# riser-1u-ethernet.net
KiCad netlist of a schematic drawn in EAGLE
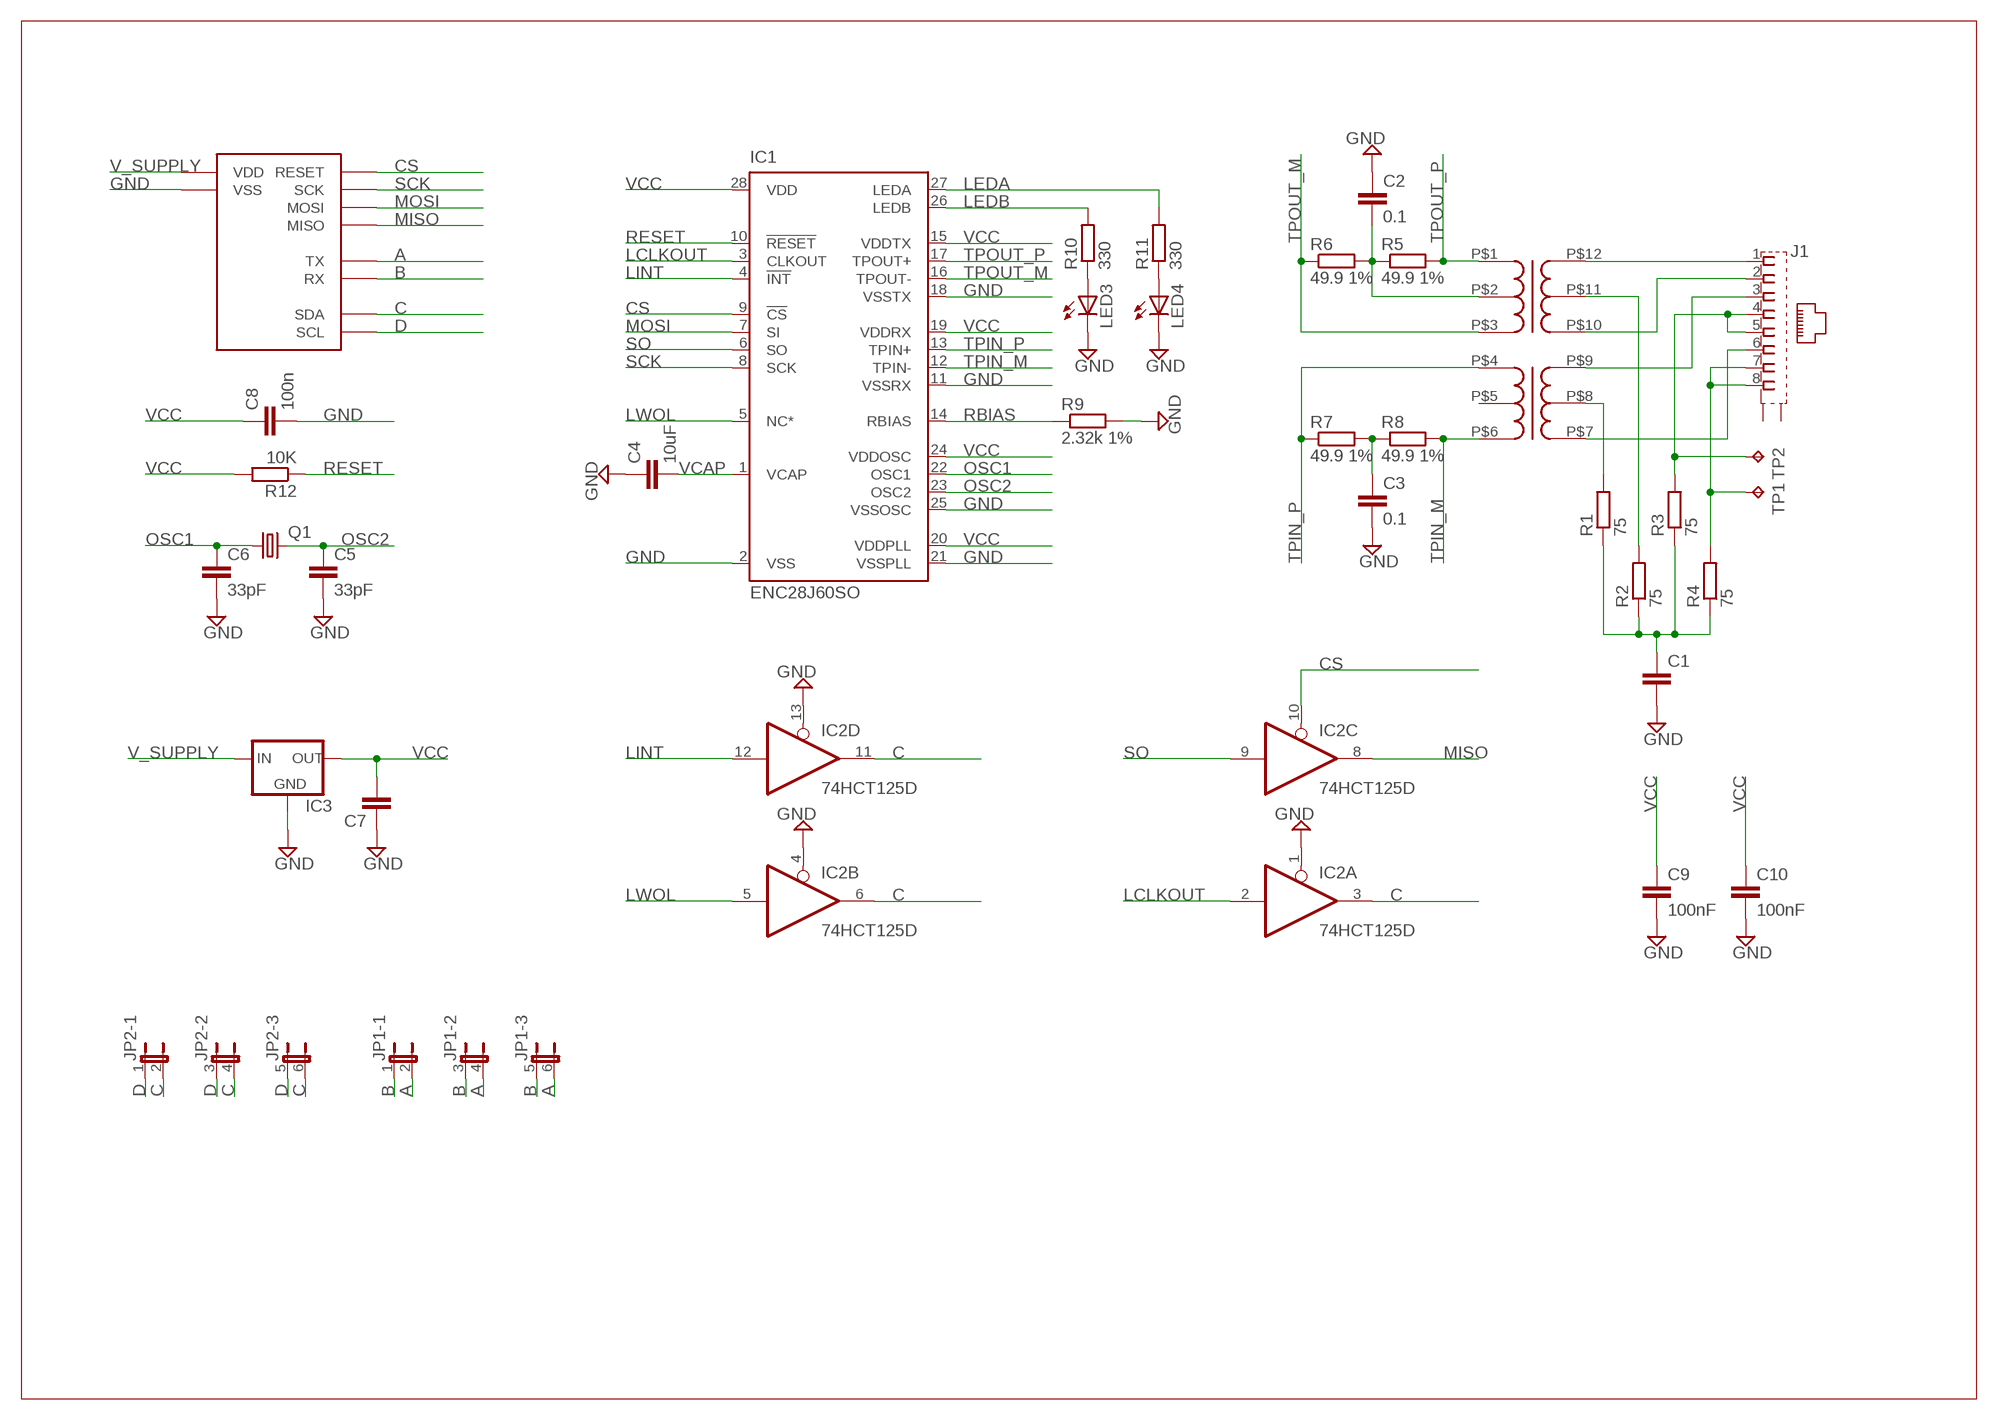
[diagram p0: schematic, sheet 1]

(export (version "E")
  (design (tool "Eeschema 10.0.6"))
  (components
    (comp (ref "C1")
      (value "C-EU075-032X103")
      (footprint "eagle-import:C075-032X103")
      (libsource (lib "eagle-import") (part "C-EU075-032X103"))
    )
    (comp (ref "C2")
      (value "0.1")
      (footprint "eagle-import:C0805")
      (libsource (lib "eagle-import") (part "C-EUC0805"))
    )
    (comp (ref "C3")
      (value "0.1")
      (footprint "eagle-import:C0805")
      (libsource (lib "eagle-import") (part "C-EUC0805"))
    )
    (comp (ref "C4")
      (value "10uF")
      (footprint "eagle-import:C1206")
      (libsource (lib "eagle-import") (part "C-EUC1206"))
    )
    (comp (ref "C5")
      (value "33pF")
      (footprint "eagle-import:C0805")
      (libsource (lib "eagle-import") (part "C-EUC0805"))
    )
    (comp (ref "C6")
      (value "33pF")
      (footprint "eagle-import:C0805")
      (libsource (lib "eagle-import") (part "C-EUC0805"))
    )
    (comp (ref "C7")
      (value "C-EUC1206")
      (footprint "eagle-import:C1206")
      (libsource (lib "eagle-import") (part "C-EUC1206"))
    )
    (comp (ref "C8")
      (value "100n")
      (footprint "eagle-import:C0805")
      (libsource (lib "eagle-import") (part "C-EUC0805"))
    )
    (comp (ref "C9")
      (value "100nF")
      (footprint "eagle-import:C0805")
      (libsource (lib "eagle-import") (part "C-EUC0805"))
    )
    (comp (ref "C10")
      (value "100nF")
      (footprint "eagle-import:C0805")
      (libsource (lib "eagle-import") (part "C-EUC0805"))
    )
    (comp (ref "IC1")
      (value "ENC28J60SO")
      (footprint "eagle-import:SO28W")
      (libsource (lib "eagle-import") (part "ENC28J60SO"))
    )
    (comp (ref "IC2")
      (value "74HCT125D")
      (footprint "eagle-import:SO14")
      (libsource (lib "eagle-import") (part "74125DHCT"))
    )
    (comp (ref "IC3")
      (value "LM1117TO252")
      (footprint "eagle-import:TO252")
      (libsource (lib "eagle-import") (part "LM1117TO252"))
    )
    (comp (ref "J1")
      (value "555153-1")
      (footprint "eagle-import:555153-1")
      (libsource (lib "eagle-import") (part "555153-1"))
    )
    (comp (ref "JP1")
      (value "JP3QE")
      (footprint "eagle-import:JP3Q")
      (libsource (lib "eagle-import") (part "JP3QE"))
    )
    (comp (ref "JP2")
      (value "JP3QE")
      (footprint "eagle-import:JP3Q")
      (libsource (lib "eagle-import") (part "JP3QE"))
    )
    (comp (ref "LED3")
      (value "LED3MM")
      (footprint "eagle-import:LED3MM")
      (libsource (lib "eagle-import") (part "LED3MM"))
    )
    (comp (ref "LED4")
      (value "LED3MM")
      (footprint "eagle-import:LED3MM")
      (libsource (lib "eagle-import") (part "LED3MM"))
    )
    (comp (ref "Q1")
      (value "CRYSTALHC49S")
      (footprint "eagle-import:HC49_S")
      (libsource (lib "eagle-import") (part "CRYSTALHC49S"))
    )
    (comp (ref "R1")
      (value "75")
      (footprint "eagle-import:R0805")
      (libsource (lib "eagle-import") (part "R-EU_R0805"))
    )
    (comp (ref "R2")
      (value "75")
      (footprint "eagle-import:R0805")
      (libsource (lib "eagle-import") (part "R-EU_R0805"))
    )
    (comp (ref "R3")
      (value "75")
      (footprint "eagle-import:R0805")
      (libsource (lib "eagle-import") (part "R-EU_R0805"))
    )
    (comp (ref "R4")
      (value "75")
      (footprint "eagle-import:R0805")
      (libsource (lib "eagle-import") (part "R-EU_R0805"))
    )
    (comp (ref "R5")
      (value "49.9 1%")
      (footprint "eagle-import:R0805")
      (libsource (lib "eagle-import") (part "R-EU_R0805"))
    )
    (comp (ref "R6")
      (value "49.9 1%")
      (footprint "eagle-import:R0805")
      (libsource (lib "eagle-import") (part "R-EU_R0805"))
    )
    (comp (ref "R7")
      (value "49.9 1%")
      (footprint "eagle-import:R0805")
      (libsource (lib "eagle-import") (part "R-EU_R0805"))
    )
    (comp (ref "R8")
      (value "49.9 1%")
      (footprint "eagle-import:R0805")
      (libsource (lib "eagle-import") (part "R-EU_R0805"))
    )
    (comp (ref "R9")
      (value "2.32k 1%")
      (footprint "eagle-import:R0805")
      (libsource (lib "eagle-import") (part "R-EU_R0805"))
    )
    (comp (ref "R10")
      (value "330")
      (footprint "eagle-import:R0805")
      (libsource (lib "eagle-import") (part "R-EU_R0805"))
    )
    (comp (ref "R11")
      (value "330")
      (footprint "eagle-import:R0805")
      (libsource (lib "eagle-import") (part "R-EU_R0805"))
    )
    (comp (ref "R12")
      (value "10K")
      (footprint "eagle-import:R0805")
      (libsource (lib "eagle-import") (part "R-EU_R0805"))
    )
    (comp (ref "TP1")
      (value "TPPAD1-13")
      (footprint "eagle-import:P1-13")
      (libsource (lib "eagle-import") (part "TPPAD1-13"))
    )
    (comp (ref "TP2")
      (value "TPPAD1-13")
      (footprint "eagle-import:P1-13")
      (libsource (lib "eagle-import") (part "TPPAD1-13"))
    )
    (comp (ref "U$1")
      (value "UNI_BOARD_CONNECTOR_10")
      (footprint "eagle-import:UNI_BOARD_CONN_10")
      (libsource (lib "eagle-import") (part "UNI_BOARD_CONNECTOR_10"))
    )
    (comp (ref "U$2")
      (value "ETHERNET_TRANSFORMER")
      (footprint "eagle-import:DIL-16-TRANSFORMER")
      (libsource (lib "eagle-import") (part "ETHERNET_TRANSFORMER"))
    )
  )
  (nets
    (net (code "1") (name "/A") (class "Default")
      (node (ref "JP1") (pin "2") (pinfunction "2_2") (pintype "passive"))
      (node (ref "JP1") (pin "4") (pinfunction "2_4") (pintype "passive"))
      (node (ref "JP1") (pin "6") (pinfunction "2_6") (pintype "passive"))
      (node (ref "U$1") (pin "C$7") (pinfunction "TX_C$7") (pintype "bidirectional"))
    )
    (net (code "2") (name "/B") (class "Default")
      (node (ref "JP1") (pin "1") (pinfunction "1_1") (pintype "passive"))
      (node (ref "JP1") (pin "3") (pinfunction "1_3") (pintype "passive"))
      (node (ref "JP1") (pin "5") (pinfunction "1_5") (pintype "passive"))
      (node (ref "U$1") (pin "C$9") (pinfunction "RX_C$9") (pintype "bidirectional"))
    )
    (net (code "3") (name "/C") (class "Default")
      (node (ref "IC2") (pin "11") (pinfunction "O_11") (pintype "tri_state"))
      (node (ref "IC2") (pin "3") (pinfunction "O_3") (pintype "tri_state"))
      (node (ref "IC2") (pin "6") (pinfunction "O_6") (pintype "tri_state"))
      (node (ref "JP2") (pin "2") (pinfunction "2_2") (pintype "passive"))
      (node (ref "JP2") (pin "4") (pinfunction "2_4") (pintype "passive"))
      (node (ref "JP2") (pin "6") (pinfunction "2_6") (pintype "passive"))
      (node (ref "U$1") (pin "C$8") (pinfunction "SDA_C$8") (pintype "bidirectional"))
    )
    (net (code "4") (name "/CS") (class "Default")
      (node (ref "IC1") (pin "9") (pinfunction "~{CS}_9") (pintype "input"))
      (node (ref "IC2") (pin "10") (pinfunction "OE_10") (pintype "input"))
      (node (ref "U$1") (pin "C$5") (pinfunction "RESET_C$5") (pintype "bidirectional"))
    )
    (net (code "5") (name "/D") (class "Default")
      (node (ref "JP2") (pin "1") (pinfunction "1_1") (pintype "passive"))
      (node (ref "JP2") (pin "3") (pinfunction "1_3") (pintype "passive"))
      (node (ref "JP2") (pin "5") (pinfunction "1_5") (pintype "passive"))
      (node (ref "U$1") (pin "C$10") (pinfunction "SCL_C$10") (pintype "bidirectional"))
    )
    (net (code "6") (name "/LCLKOUT") (class "Default")
      (node (ref "IC1") (pin "3") (pinfunction "CLKOUT_3") (pintype "output"))
      (node (ref "IC2") (pin "2") (pinfunction "I_2") (pintype "input"))
    )
    (net (code "7") (name "/LEDA") (class "Default")
      (node (ref "IC1") (pin "27") (pinfunction "LEDA_27") (pintype "output"))
      (node (ref "R11") (pin "2") (pinfunction "2_2") (pintype "passive"))
    )
    (net (code "8") (name "/LEDB") (class "Default")
      (node (ref "IC1") (pin "26") (pinfunction "LEDB_26") (pintype "output"))
      (node (ref "R10") (pin "2") (pinfunction "2_2") (pintype "passive"))
    )
    (net (code "9") (name "/LINT") (class "Default")
      (node (ref "IC1") (pin "4") (pinfunction "~{INT}_4") (pintype "output"))
      (node (ref "IC2") (pin "12") (pinfunction "I_12") (pintype "input"))
    )
    (net (code "10") (name "/LWOL") (class "Default")
      (node (ref "IC1") (pin "5") (pinfunction "NC*_5") (pintype "output"))
      (node (ref "IC2") (pin "5") (pinfunction "I_5") (pintype "input"))
    )
    (net (code "11") (name "/MISO") (class "Default")
      (node (ref "IC2") (pin "8") (pinfunction "O_8") (pintype "tri_state"))
      (node (ref "U$1") (pin "C$1") (pinfunction "MISO_C$1") (pintype "bidirectional"))
    )
    (net (code "12") (name "/MOSI") (class "Default")
      (node (ref "IC1") (pin "7") (pinfunction "SI_7") (pintype "input"))
      (node (ref "U$1") (pin "C$4") (pinfunction "MOSI_C$4") (pintype "bidirectional"))
    )
    (net (code "13") (name "/OSC1") (class "Default")
      (node (ref "C6") (pin "1") (pinfunction "1_1") (pintype "passive"))
      (node (ref "IC1") (pin "22") (pinfunction "OSC1_22") (pintype "input"))
      (node (ref "Q1") (pin "1") (pinfunction "1_1") (pintype "passive"))
    )
    (net (code "14") (name "/OSC2") (class "Default")
      (node (ref "C5") (pin "1") (pinfunction "1_1") (pintype "passive"))
      (node (ref "IC1") (pin "23") (pinfunction "OSC2_23") (pintype "output"))
      (node (ref "Q1") (pin "2") (pinfunction "2_2") (pintype "passive"))
    )
    (net (code "15") (name "/RBIAS") (class "Default")
      (node (ref "IC1") (pin "14") (pinfunction "RBIAS_14") (pintype "input"))
      (node (ref "R9") (pin "1") (pinfunction "1_1") (pintype "passive"))
    )
    (net (code "16") (name "/RESET") (class "Default")
      (node (ref "IC1") (pin "10") (pinfunction "~{RESET}_10") (pintype "input"))
      (node (ref "R12") (pin "1") (pinfunction "1_1") (pintype "passive"))
    )
    (net (code "17") (name "/SCK") (class "Default")
      (node (ref "IC1") (pin "8") (pinfunction "SCK_8") (pintype "input"))
      (node (ref "U$1") (pin "C$3") (pinfunction "SCK_C$3") (pintype "bidirectional"))
    )
    (net (code "18") (name "/SO") (class "Default")
      (node (ref "IC1") (pin "6") (pinfunction "SO_6") (pintype "output"))
      (node (ref "IC2") (pin "9") (pinfunction "I_9") (pintype "input"))
    )
    (net (code "19") (name "/TPIN_M") (class "Default")
      (node (ref "IC1") (pin "12") (pinfunction "TPIN-_12") (pintype "input"))
      (node (ref "R8") (pin "2") (pinfunction "2_2") (pintype "passive"))
      (node (ref "U$2") (pin "P$6") (pinfunction "P8_P$6") (pintype "bidirectional"))
    )
    (net (code "20") (name "/TPIN_P") (class "Default")
      (node (ref "IC1") (pin "13") (pinfunction "TPIN+_13") (pintype "input"))
      (node (ref "R7") (pin "1") (pinfunction "1_1") (pintype "passive"))
      (node (ref "U$2") (pin "P$4") (pinfunction "P6_P$4") (pintype "bidirectional"))
    )
    (net (code "21") (name "/TPOUT_M") (class "Default")
      (node (ref "IC1") (pin "16") (pinfunction "TPOUT-_16") (pintype "output"))
      (node (ref "R6") (pin "1") (pinfunction "1_1") (pintype "passive"))
      (node (ref "U$2") (pin "P$3") (pinfunction "P3_P$3") (pintype "bidirectional"))
    )
    (net (code "22") (name "/TPOUT_P") (class "Default")
      (node (ref "IC1") (pin "17") (pinfunction "TPOUT+_17") (pintype "output"))
      (node (ref "R5") (pin "2") (pinfunction "2_2") (pintype "passive"))
      (node (ref "U$2") (pin "P$1") (pinfunction "P1_P$1") (pintype "bidirectional"))
    )
    (net (code "23") (name "/VCAP") (class "Default")
      (node (ref "C4") (pin "2") (pinfunction "2_2") (pintype "passive"))
      (node (ref "IC1") (pin "1") (pinfunction "VCAP_1") (pintype "input"))
    )
    (net (code "24") (name "/VCC") (class "Default")
      (node (ref "C10") (pin "1") (pinfunction "1_1") (pintype "passive"))
      (node (ref "C7") (pin "2") (pinfunction "2_2") (pintype "passive"))
      (node (ref "C8") (pin "1") (pinfunction "1_1") (pintype "passive"))
      (node (ref "C9") (pin "1") (pinfunction "1_1") (pintype "passive"))
      (node (ref "IC1") (pin "15") (pinfunction "VDDTX_15") (pintype "input"))
      (node (ref "IC1") (pin "19") (pinfunction "VDDRX_19") (pintype "input"))
      (node (ref "IC1") (pin "20") (pinfunction "VDDPLL_20") (pintype "input"))
      (node (ref "IC1") (pin "24") (pinfunction "VDDOSC_24") (pintype "input"))
      (node (ref "IC1") (pin "28") (pinfunction "VDD_28") (pintype "input"))
      (node (ref "IC3") (pin "3") (pinfunction "OUT_3") (pintype "passive"))
      (node (ref "R12") (pin "2") (pinfunction "2_2") (pintype "passive"))
    )
    (net (code "25") (name "/V_SUPPLY") (class "Default")
      (node (ref "IC3") (pin "2") (pinfunction "IN_2") (pintype "input"))
      (node (ref "U$1") (pin "C$2") (pinfunction "VDD_C$2") (pintype "power_in"))
    )
    (net (code "26") (name "GND") (class "Default")
      (node (ref "C1") (pin "2") (pinfunction "2_2") (pintype "passive"))
      (node (ref "C10") (pin "2") (pinfunction "2_2") (pintype "passive"))
      (node (ref "C2") (pin "1") (pinfunction "1_1") (pintype "passive"))
      (node (ref "C3") (pin "2") (pinfunction "2_2") (pintype "passive"))
      (node (ref "C4") (pin "1") (pinfunction "1_1") (pintype "passive"))
      (node (ref "C5") (pin "2") (pinfunction "2_2") (pintype "passive"))
      (node (ref "C6") (pin "2") (pinfunction "2_2") (pintype "passive"))
      (node (ref "C7") (pin "1") (pinfunction "1_1") (pintype "passive"))
      (node (ref "C8") (pin "2") (pinfunction "2_2") (pintype "passive"))
      (node (ref "C9") (pin "2") (pinfunction "2_2") (pintype "passive"))
      (node (ref "IC1") (pin "11") (pinfunction "VSSRX_11") (pintype "input"))
      (node (ref "IC1") (pin "18") (pinfunction "VSSTX_18") (pintype "input"))
      (node (ref "IC1") (pin "2") (pinfunction "VSS_2") (pintype "input"))
      (node (ref "IC1") (pin "21") (pinfunction "VSSPLL_21") (pintype "input"))
      (node (ref "IC1") (pin "25") (pinfunction "VSSOSC_25") (pintype "input"))
      (node (ref "IC2") (pin "1") (pinfunction "OE_1") (pintype "input"))
      (node (ref "IC2") (pin "13") (pinfunction "OE_13") (pintype "input"))
      (node (ref "IC2") (pin "4") (pinfunction "OE_4") (pintype "input"))
      (node (ref "IC3") (pin "1") (pinfunction "GND_1") (pintype "input"))
      (node (ref "LED3") (pin "K") (pinfunction "C_K") (pintype "passive"))
      (node (ref "LED4") (pin "K") (pinfunction "C_K") (pintype "passive"))
      (node (ref "R9") (pin "2") (pinfunction "2_2") (pintype "passive"))
      (node (ref "U$1") (pin "C$6") (pinfunction "VSS_C$6") (pintype "power_in"))
    )
    (net (code "27") (name "Net-(C1-Pad1)") (class "Default")
      (node (ref "C1") (pin "1") (pinfunction "1_1") (pintype "passive"))
      (node (ref "R1") (pin "1") (pinfunction "1_1") (pintype "passive"))
      (node (ref "R2") (pin "1") (pinfunction "1_1") (pintype "passive"))
      (node (ref "R3") (pin "1") (pinfunction "1_1") (pintype "passive"))
      (node (ref "R4") (pin "1") (pinfunction "1_1") (pintype "passive"))
    )
    (net (code "28") (name "Net-(C3-Pad1)") (class "Default")
      (node (ref "C3") (pin "1") (pinfunction "1_1") (pintype "passive"))
      (node (ref "R7") (pin "2") (pinfunction "2_2") (pintype "passive"))
      (node (ref "R8") (pin "1") (pinfunction "1_1") (pintype "passive"))
    )
    (net (code "29") (name "Net-(J1-Pad4)") (class "Default")
      (node (ref "J1") (pin "4") (pinfunction "4_4") (pintype "passive"))
      (node (ref "J1") (pin "5") (pinfunction "5_5") (pintype "passive"))
      (node (ref "R3") (pin "2") (pinfunction "2_2") (pintype "passive"))
      (node (ref "TP2") (pin "TP") (pinfunction "TP_TP") (pintype "input"))
    )
    (net (code "30") (name "Net-(J1-Pad7)") (class "Default")
      (node (ref "J1") (pin "7") (pinfunction "7_7") (pintype "passive"))
      (node (ref "J1") (pin "8") (pinfunction "8_8") (pintype "passive"))
      (node (ref "R4") (pin "2") (pinfunction "2_2") (pintype "passive"))
      (node (ref "TP1") (pin "TP") (pinfunction "TP_TP") (pintype "input"))
    )
    (net (code "31") (name "Net-(LED3-PadA)") (class "Default")
      (node (ref "LED3") (pin "A") (pinfunction "A_A") (pintype "passive"))
      (node (ref "R10") (pin "1") (pinfunction "1_1") (pintype "passive"))
    )
    (net (code "32") (name "Net-(LED4-PadA)") (class "Default")
      (node (ref "LED4") (pin "A") (pinfunction "A_A") (pintype "passive"))
      (node (ref "R11") (pin "1") (pinfunction "1_1") (pintype "passive"))
    )
    (net (code "33") (name "Net-(U$2-P2)") (class "Default")
      (node (ref "C2") (pin "2") (pinfunction "2_2") (pintype "passive"))
      (node (ref "R5") (pin "1") (pinfunction "1_1") (pintype "passive"))
      (node (ref "R6") (pin "2") (pinfunction "2_2") (pintype "passive"))
      (node (ref "U$2") (pin "P$2") (pinfunction "P2_P$2") (pintype "bidirectional"))
    )
    (net (code "34") (name "Net-(U$2-P9)") (class "Default")
      (node (ref "J1") (pin "6") (pinfunction "6_6") (pintype "passive"))
      (node (ref "U$2") (pin "P$7") (pinfunction "P9_P$7") (pintype "bidirectional"))
    )
    (net (code "35") (name "Net-(U$2-P10)") (class "Default")
      (node (ref "R1") (pin "2") (pinfunction "2_2") (pintype "passive"))
      (node (ref "U$2") (pin "P$8") (pinfunction "P10_P$8") (pintype "bidirectional"))
    )
    (net (code "36") (name "Net-(U$2-P11)") (class "Default")
      (node (ref "J1") (pin "3") (pinfunction "3_3") (pintype "passive"))
      (node (ref "U$2") (pin "P$9") (pinfunction "P11_P$9") (pintype "bidirectional"))
    )
    (net (code "37") (name "Net-(U$2-P14)") (class "Default")
      (node (ref "J1") (pin "2") (pinfunction "2_2") (pintype "passive"))
      (node (ref "U$2") (pin "P$10") (pinfunction "P14_P$10") (pintype "bidirectional"))
    )
    (net (code "38") (name "Net-(U$2-P15)") (class "Default")
      (node (ref "R2") (pin "2") (pinfunction "2_2") (pintype "passive"))
      (node (ref "U$2") (pin "P$11") (pinfunction "P15_P$11") (pintype "bidirectional"))
    )
    (net (code "39") (name "Net-(U$2-P16)") (class "Default")
      (node (ref "J1") (pin "1") (pinfunction "1_1") (pintype "passive"))
      (node (ref "U$2") (pin "P$12") (pinfunction "P16_P$12") (pintype "bidirectional"))
    )
    (net (code "40") (name "unconnected-(J1-S1-PadG1)") (class "Default")
      (node (ref "J1") (pin "G1") (pinfunction "S1_G1") (pintype "passive"))
    )
    (net (code "41") (name "unconnected-(J1-S2-PadG2)") (class "Default")
      (node (ref "J1") (pin "G2") (pinfunction "S2_G2") (pintype "passive"))
    )
    (net (code "42") (name "unconnected-(U$2-P7-PadP$5)") (class "Default")
      (node (ref "U$2") (pin "P$5") (pinfunction "P7_P$5") (pintype "bidirectional"))
    )
  )
)
